# Controller_Watchdog.net
KiCad netlist of a schematic drawn in Altium Designer
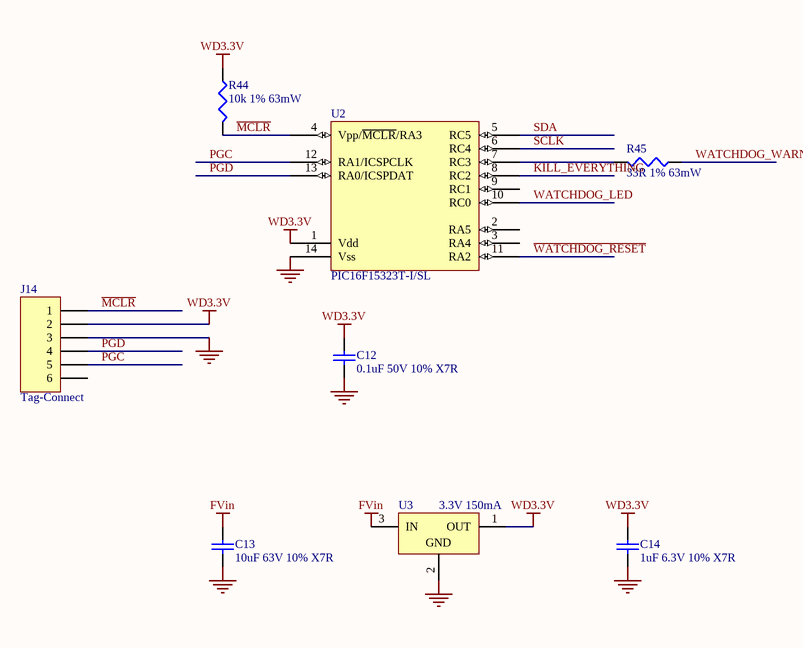
[diagram p0: Controller Watchdog.SchDoc]

(export (version "E")
  (design (tool "Eeschema 10.0.6"))
  (components
    (comp (ref "C12")
      (value "0.1uF 50V 10% X7R")
      (footprint "CAPC1005L")
      (description "Capacitor")
      (libsource (lib "Miscellaneous Devices") (part "Cap"))
    )
    (comp (ref "C13")
      (value "10uF 63V 10% X7R")
      (footprint "C1210_L")
      (description "Capacitor")
      (libsource (lib "Miscellaneous Devices") (part "Cap"))
    )
    (comp (ref "C14")
      (value "1uF 6.3V 10% X7R")
      (footprint "CAPC1005L")
      (description "Capacitor")
      (libsource (lib "Miscellaneous Devices") (part "Cap"))
    )
    (comp (ref "J14")
      (value "Tag-Connect")
      (footprint "TC2030-MCP")
      (description "Tag Connect Programming Header")
      (libsource (lib "Miscellaneous Connectors") (part "Header 6"))
    )
    (comp (ref "R44")
      (value "10k 1% 63mW")
      (footprint "RESC1005L")
      (description "Resistor")
      (libsource (lib "Miscellaneous Devices") (part "Res3"))
    )
    (comp (ref "R45")
      (value "33R 1% 63mW")
      (footprint "RESC1005L")
      (description "Resistor")
      (libsource (lib "Miscellaneous Devices") (part "Res3"))
    )
    (comp (ref "U2")
      (value "PIC16F15323T-I/SL")
      (footprint "14SOP_L")
      (description "IC MCU 8BIT 3.5KB FLASH 14SOIC")
      (fields (field (name "MANUFACTURER") "Microchip Technology"))
      (libsource (lib "Latium Component Library") (part "PIC16F15323"))
    )
    (comp (ref "U3")
      (value "3.3V 150mA")
      (footprint "SOT89L")
      (description "IC REG LINEAR 3.3V 150MA SOT89")
      (fields
        (field (name "MANUFACTURER PART NUMBER") "AP7381-33Y-13")
        (field (name "MANUFACTURER") "Diodes Incorporated")
      )
      (libsource (lib "LDO") (part "LP2954AIT"))
    )
  )
  (nets
    (net (code "1") (name "/KILL_EVERYTHING") (class "Default")
      (node (ref "U2") (pin "8") (pinfunction "RC2_8") (pintype "bidirectional"))
    )
    (net (code "2") (name "/PGC") (class "Default")
      (node (ref "J14") (pin "5") (pinfunction "5_5") (pintype "passive"))
      (node (ref "U2") (pin "12") (pinfunction "RA1/ICSPCLK_12") (pintype "bidirectional"))
    )
    (net (code "3") (name "/PGD") (class "Default")
      (node (ref "J14") (pin "4") (pinfunction "4_4") (pintype "passive"))
      (node (ref "U2") (pin "13") (pinfunction "RA0/ICSPDAT_13") (pintype "bidirectional"))
    )
    (net (code "4") (name "/SCLK") (class "Default")
      (node (ref "U2") (pin "6") (pinfunction "RC4_6") (pintype "bidirectional"))
    )
    (net (code "5") (name "/SDA") (class "Default")
      (node (ref "U2") (pin "5") (pinfunction "RC5_5") (pintype "bidirectional"))
    )
    (net (code "6") (name "/WATCHDOG_LED") (class "Default")
      (node (ref "U2") (pin "10") (pinfunction "RC0_10") (pintype "bidirectional"))
    )
    (net (code "7") (name "/WATCHDOG_WARN") (class "Default")
      (node (ref "R45") (pin "2") (pinfunction "2_2") (pintype "passive"))
    )
    (net (code "8") (name "/~{MCLR}") (class "Default")
      (node (ref "J14") (pin "1") (pinfunction "1_1") (pintype "passive"))
      (node (ref "R44") (pin "2") (pinfunction "2_2") (pintype "passive"))
      (node (ref "U2") (pin "4") (pinfunction "Vpp/~{MCLR}/RA3_4") (pintype "bidirectional"))
    )
    (net (code "9") (name "/~{WATCHDOG_RESET}") (class "Default")
      (node (ref "U2") (pin "11") (pinfunction "RA2_11") (pintype "bidirectional"))
    )
    (net (code "10") (name "FVin") (class "Default")
      (node (ref "C13") (pin "2") (pinfunction "2_2") (pintype "passive"))
      (node (ref "U3") (pin "3") (pinfunction "IN_3") (pintype "power_in"))
    )
    (net (code "11") (name "GND") (class "Default")
      (node (ref "C12") (pin "2") (pinfunction "2_2") (pintype "passive"))
      (node (ref "C13") (pin "1") (pinfunction "1_1") (pintype "passive"))
      (node (ref "C14") (pin "2") (pinfunction "2_2") (pintype "passive"))
      (node (ref "J14") (pin "3") (pinfunction "3_3") (pintype "passive"))
      (node (ref "U2") (pin "14") (pinfunction "Vss_14") (pintype "power_in"))
      (node (ref "U3") (pin "2") (pinfunction "GND_2") (pintype "power_in"))
    )
    (net (code "12") (name "Net-(U2-RC3)") (class "Default")
      (node (ref "R45") (pin "1") (pinfunction "1_1") (pintype "passive"))
      (node (ref "U2") (pin "7") (pinfunction "RC3_7") (pintype "bidirectional"))
    )
    (net (code "13") (name "WD3.3V") (class "Default")
      (node (ref "C12") (pin "1") (pinfunction "1_1") (pintype "passive"))
      (node (ref "C14") (pin "1") (pinfunction "1_1") (pintype "passive"))
      (node (ref "J14") (pin "2") (pinfunction "2_2") (pintype "passive"))
      (node (ref "R44") (pin "1") (pinfunction "1_1") (pintype "passive"))
      (node (ref "U2") (pin "1") (pinfunction "Vdd_1") (pintype "power_in"))
      (node (ref "U3") (pin "1") (pinfunction "OUT_1") (pintype "power_in"))
    )
    (net (code "14") (name "unconnected-(J14-Pad6)") (class "Default")
      (node (ref "J14") (pin "6") (pinfunction "6_6") (pintype "passive"))
    )
    (net (code "15") (name "unconnected-(U2-RA4-Pad3)") (class "Default")
      (node (ref "U2") (pin "3") (pinfunction "RA4_3") (pintype "bidirectional"))
    )
    (net (code "16") (name "unconnected-(U2-RA5-Pad2)") (class "Default")
      (node (ref "U2") (pin "2") (pinfunction "RA5_2") (pintype "bidirectional"))
    )
    (net (code "17") (name "unconnected-(U2-RC1-Pad9)") (class "Default")
      (node (ref "U2") (pin "9") (pinfunction "RC1_9") (pintype "bidirectional"))
    )
  )
)
